# PL2303.net
KiCad netlist of a schematic drawn in Altium Designer
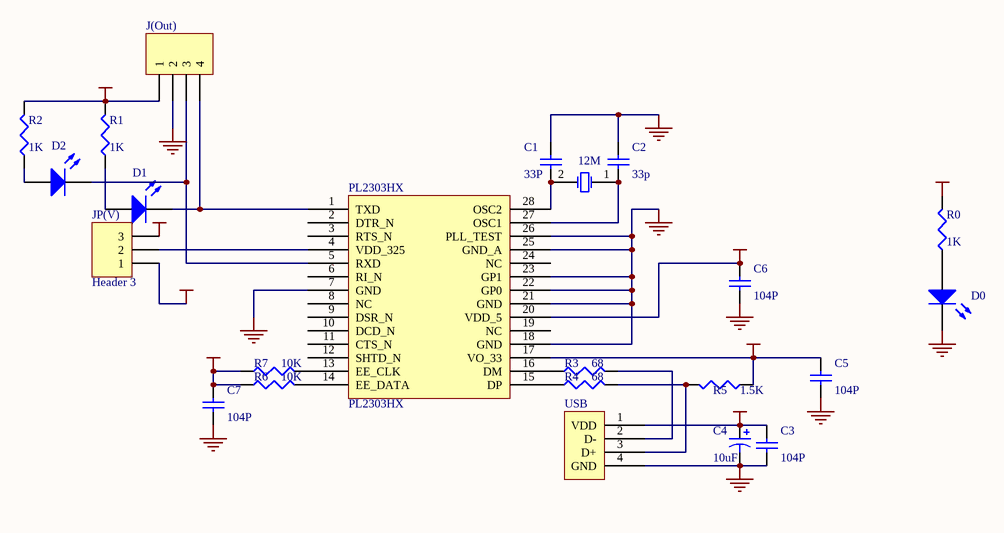
[diagram p0: PL2303.SchDoc]

(export (version "E")
  (design (tool "Eeschema 10.0.6"))
  (components
    (comp (ref "12M")
      (value "XTAL")
      (footprint "RAD-0.2")
      (description "Crystal Oscillator")
      (fields (field (name "PUBLISHER") "Altium Limited"))
      (libsource (lib "Miscellaneous Devices") (part "XTAL"))
    )
    (comp (ref "C1")
      (value "33P")
      (footprint "CR2012-0805")
      (description "Capacitor")
      (fields (field (name "Comment") "Cap") (field (name "PUBLISHER") "Altium Limited"))
      (libsource (lib "Miscellaneous Devices") (part "Cap"))
    )
    (comp (ref "C2")
      (value "33p")
      (footprint "CR2012-0805")
      (description "Capacitor")
      (fields (field (name "Comment") "Cap") (field (name "PUBLISHER") "Altium Limited"))
      (libsource (lib "Miscellaneous Devices") (part "Cap"))
    )
    (comp (ref "C3")
      (value "104P")
      (footprint "CR2012-0805")
      (description "Capacitor")
      (fields (field (name "Comment") "Cap") (field (name "PUBLISHER") "Altium Limited"))
      (libsource (lib "Miscellaneous Devices") (part "Cap"))
    )
    (comp (ref "C4")
      (value "10uF")
      (footprint "CR3225-1210")
      (description "Polarized Capacitor (Axial)")
      (fields (field (name "Comment") "Cap Pol2") (field (name "PUBLISHER") "Altium Limited"))
      (libsource (lib "Miscellaneous Devices") (part "Cap Pol2"))
    )
    (comp (ref "C5")
      (value "104P")
      (footprint "CR2012-0805")
      (description "Capacitor")
      (fields (field (name "Comment") "Cap") (field (name "PUBLISHER") "Altium Limited"))
      (libsource (lib "Miscellaneous Devices") (part "Cap"))
    )
    (comp (ref "C6")
      (value "104P")
      (footprint "CR2012-0805")
      (description "Capacitor")
      (fields (field (name "Comment") "Cap") (field (name "PUBLISHER") "Altium Limited"))
      (libsource (lib "Miscellaneous Devices") (part "Cap"))
    )
    (comp (ref "C7")
      (value "104P")
      (footprint "CR2012-0805")
      (description "Capacitor")
      (fields (field (name "Comment") "Cap") (field (name "PUBLISHER") "Altium Limited"))
      (libsource (lib "Miscellaneous Devices") (part "Cap"))
    )
    (comp (ref "D0")
      (value "LED2")
      (footprint "R2012-0805")
      (description "Typical RED, GREEN, YELLOW, AMBER GaAs LED")
      (fields (field (name "PUBLISHER") "Altium Limited"))
      (libsource (lib "Miscellaneous Devices") (part "LED2"))
    )
    (comp (ref "D1")
      (value "LED2")
      (footprint "R2012-0805")
      (description "Typical RED, GREEN, YELLOW, AMBER GaAs LED")
      (fields (field (name "PUBLISHER") "Altium Limited"))
      (libsource (lib "Miscellaneous Devices") (part "LED2"))
    )
    (comp (ref "D2")
      (value "LED2")
      (footprint "R2012-0805")
      (description "Typical RED, GREEN, YELLOW, AMBER GaAs LED")
      (fields (field (name "PUBLISHER") "Altium Limited"))
      (libsource (lib "Miscellaneous Devices") (part "LED2"))
    )
    (comp (ref "J(Out)")
      (value "Header 4")
      (footprint "HDR1X4")
      (description "Header, 4-Pin")
      (fields (field (name "PUBLISHER") "Altium Limited"))
      (libsource (lib "Miscellaneous Connectors") (part "Header 4"))
    )
    (comp (ref "JP(V)")
      (value "Header 3")
      (footprint "HDR1X3")
      (description "Header, 3-Pin")
      (fields (field (name "PUBLISHER") "Altium Limited"))
      (libsource (lib "Miscellaneous Connectors") (part "Header 3"))
    )
    (comp (ref "PL2303HX") (value "PL2303HX") (footprint "SSOP28") (libsource (lib "PL2303") (part "PL2303")))
    (comp (ref "R0")
      (value "1K")
      (footprint "R2012-0805")
      (description "Resistor")
      (fields (field (name "Comment") "Res3") (field (name "PUBLISHER") "Altium Limited"))
      (libsource (lib "Miscellaneous Devices") (part "Res3"))
    )
    (comp (ref "R1")
      (value "1K")
      (footprint "R2012-0805")
      (description "Resistor")
      (fields (field (name "Comment") "Res3") (field (name "PUBLISHER") "Altium Limited"))
      (libsource (lib "Miscellaneous Devices") (part "Res3"))
    )
    (comp (ref "R2")
      (value "1K")
      (footprint "R2012-0805")
      (description "Resistor")
      (fields (field (name "Comment") "Res3") (field (name "PUBLISHER") "Altium Limited"))
      (libsource (lib "Miscellaneous Devices") (part "Res3"))
    )
    (comp (ref "R3")
      (value "68")
      (footprint "CR2012-0805")
      (description "Resistor")
      (fields (field (name "Comment") "Res3") (field (name "PUBLISHER") "Altium Limited"))
      (libsource (lib "Miscellaneous Devices") (part "Res3"))
    )
    (comp (ref "R4")
      (value "68")
      (footprint "CR2012-0805")
      (description "Resistor")
      (fields (field (name "Comment") "Res3") (field (name "PUBLISHER") "Altium Limited"))
      (libsource (lib "Miscellaneous Devices") (part "Res3"))
    )
    (comp (ref "R5")
      (value "1.5K")
      (footprint "CR2012-0805")
      (description "Resistor")
      (fields (field (name "Comment") "Res3") (field (name "PUBLISHER") "Altium Limited"))
      (libsource (lib "Miscellaneous Devices") (part "Res3"))
    )
    (comp (ref "R6")
      (value "10K")
      (footprint "CR2012-0805")
      (description "Resistor")
      (fields (field (name "Comment") "Res3") (field (name "PUBLISHER") "Altium Limited"))
      (libsource (lib "Miscellaneous Devices") (part "Res3"))
    )
    (comp (ref "R7")
      (value "10K")
      (footprint "CR2012-0805")
      (description "Resistor")
      (fields (field (name "Comment") "Res3") (field (name "PUBLISHER") "Altium Limited"))
      (libsource (lib "Miscellaneous Devices") (part "Res3"))
    )
    (comp (ref "USB") (value "USB") (footprint "mini_USB") (libsource (lib "USB") (part "USB")))
  )
  (nets
    (net (code "1") (name "GND") (class "Default")
      (node (ref "C1") (pin "2") (pinfunction "2_2") (pintype "passive"))
      (node (ref "C2") (pin "2") (pinfunction "2_2") (pintype "passive"))
      (node (ref "C3") (pin "1") (pinfunction "1_1") (pintype "passive"))
      (node (ref "C4") (pin "2") (pinfunction "2_2") (pintype "passive"))
      (node (ref "C5") (pin "1") (pinfunction "1_1") (pintype "passive"))
      (node (ref "C6") (pin "1") (pinfunction "1_1") (pintype "passive"))
      (node (ref "C7") (pin "1") (pinfunction "1_1") (pintype "passive"))
      (node (ref "D0") (pin "2") (pinfunction "K_2") (pintype "passive"))
      (node (ref "J(Out)") (pin "2") (pinfunction "2_2") (pintype "passive"))
      (node (ref "PL2303HX") (pin "18") (pinfunction "GND_18") (pintype "passive"))
      (node (ref "PL2303HX") (pin "21") (pinfunction "GND_21") (pintype "passive"))
      (node (ref "PL2303HX") (pin "22") (pinfunction "GP0_22") (pintype "passive"))
      (node (ref "PL2303HX") (pin "23") (pinfunction "GP1_23") (pintype "passive"))
      (node (ref "PL2303HX") (pin "25") (pinfunction "GND_A_25") (pintype "passive"))
      (node (ref "PL2303HX") (pin "26") (pinfunction "PLL_TEST_26") (pintype "passive"))
      (node (ref "PL2303HX") (pin "7") (pinfunction "GND_7") (pintype "passive"))
      (node (ref "USB") (pin "4") (pinfunction "GND_4") (pintype "passive"))
    )
    (net (code "2") (name "Net-(12M-OSC1)") (class "Default")
      (node (ref "12M") (pin "1") (pinfunction "OSC1_1") (pintype "passive"))
      (node (ref "C2") (pin "1") (pinfunction "1_1") (pintype "passive"))
      (node (ref "PL2303HX") (pin "27") (pinfunction "OSC1_27") (pintype "passive"))
    )
    (net (code "3") (name "Net-(12M-OSC2)") (class "Default")
      (node (ref "12M") (pin "2") (pinfunction "OSC2_2") (pintype "passive"))
      (node (ref "C1") (pin "1") (pinfunction "1_1") (pintype "passive"))
      (node (ref "PL2303HX") (pin "28") (pinfunction "OSC2_28") (pintype "passive"))
    )
    (net (code "4") (name "Net-(D0-A)") (class "Default")
      (node (ref "D0") (pin "1") (pinfunction "A_1") (pintype "passive"))
      (node (ref "R0") (pin "1") (pinfunction "1_1") (pintype "passive"))
    )
    (net (code "5") (name "Net-(D1-A)") (class "Default")
      (node (ref "D1") (pin "1") (pinfunction "A_1") (pintype "passive"))
      (node (ref "R1") (pin "1") (pinfunction "1_1") (pintype "passive"))
    )
    (net (code "6") (name "Net-(D1-K)") (class "Default")
      (node (ref "D1") (pin "2") (pinfunction "K_2") (pintype "passive"))
      (node (ref "J(Out)") (pin "4") (pinfunction "4_4") (pintype "passive"))
      (node (ref "PL2303HX") (pin "1") (pinfunction "TXD_1") (pintype "passive"))
    )
    (net (code "7") (name "Net-(D2-A)") (class "Default")
      (node (ref "D2") (pin "1") (pinfunction "A_1") (pintype "passive"))
      (node (ref "R2") (pin "1") (pinfunction "1_1") (pintype "passive"))
    )
    (net (code "8") (name "Net-(D2-K)") (class "Default")
      (node (ref "D2") (pin "2") (pinfunction "K_2") (pintype "passive"))
      (node (ref "J(Out)") (pin "3") (pinfunction "3_3") (pintype "passive"))
      (node (ref "PL2303HX") (pin "5") (pinfunction "RXD_5") (pintype "passive"))
    )
    (net (code "9") (name "Net-(PL2303HX-DM)") (class "Default")
      (node (ref "PL2303HX") (pin "16") (pinfunction "DM_16") (pintype "passive"))
      (node (ref "R3") (pin "1") (pinfunction "1_1") (pintype "passive"))
    )
    (net (code "10") (name "Net-(PL2303HX-DP)") (class "Default")
      (node (ref "PL2303HX") (pin "15") (pinfunction "DP_15") (pintype "passive"))
      (node (ref "R4") (pin "1") (pinfunction "1_1") (pintype "passive"))
    )
    (net (code "11") (name "Net-(PL2303HX-EE_CLK)") (class "Default")
      (node (ref "PL2303HX") (pin "13") (pinfunction "EE_CLK_13") (pintype "passive"))
      (node (ref "R7") (pin "2") (pinfunction "2_2") (pintype "passive"))
    )
    (net (code "12") (name "Net-(PL2303HX-EE_DATA)") (class "Default")
      (node (ref "PL2303HX") (pin "14") (pinfunction "EE_DATA_14") (pintype "passive"))
      (node (ref "R6") (pin "2") (pinfunction "2_2") (pintype "passive"))
    )
    (net (code "13") (name "Net-(PL2303HX-VDD_325)") (class "Default")
      (node (ref "JP(V)") (pin "2") (pinfunction "2_2") (pintype "passive"))
      (node (ref "PL2303HX") (pin "4") (pinfunction "VDD_325_4") (pintype "passive"))
    )
    (net (code "14") (name "Net-(USB-D+)") (class "Default")
      (node (ref "R4") (pin "2") (pinfunction "2_2") (pintype "passive"))
      (node (ref "R5") (pin "2") (pinfunction "2_2") (pintype "passive"))
      (node (ref "USB") (pin "3") (pinfunction "D+_3") (pintype "passive"))
    )
    (net (code "15") (name "Net-(USB-D-)") (class "Default")
      (node (ref "R3") (pin "2") (pinfunction "2_2") (pintype "passive"))
      (node (ref "USB") (pin "2") (pinfunction "D-_2") (pintype "passive"))
    )
    (net (code "16") (name "VDD") (class "Default")
      (node (ref "C3") (pin "2") (pinfunction "2_2") (pintype "passive"))
      (node (ref "C4") (pin "1") (pinfunction "1_1") (pintype "passive"))
      (node (ref "C6") (pin "2") (pinfunction "2_2") (pintype "passive"))
      (node (ref "C7") (pin "2") (pinfunction "2_2") (pintype "passive"))
      (node (ref "J(Out)") (pin "1") (pinfunction "1_1") (pintype "passive"))
      (node (ref "JP(V)") (pin "3") (pinfunction "3_3") (pintype "passive"))
      (node (ref "PL2303HX") (pin "20") (pinfunction "VDD_5_20") (pintype "passive"))
      (node (ref "R0") (pin "2") (pinfunction "2_2") (pintype "passive"))
      (node (ref "R1") (pin "2") (pinfunction "2_2") (pintype "passive"))
      (node (ref "R2") (pin "2") (pinfunction "2_2") (pintype "passive"))
      (node (ref "R6") (pin "1") (pinfunction "1_1") (pintype "passive"))
      (node (ref "R7") (pin "1") (pinfunction "1_1") (pintype "passive"))
      (node (ref "USB") (pin "1") (pinfunction "VDD_1") (pintype "passive"))
    )
    (net (code "17") (name "VDD3.3") (class "Default")
      (node (ref "C5") (pin "2") (pinfunction "2_2") (pintype "passive"))
      (node (ref "JP(V)") (pin "1") (pinfunction "1_1") (pintype "passive"))
      (node (ref "PL2303HX") (pin "17") (pinfunction "VO_33_17") (pintype "passive"))
      (node (ref "R5") (pin "1") (pinfunction "1_1") (pintype "passive"))
    )
    (net (code "18") (name "unconnected-(PL2303HX-CTS_N-Pad11)") (class "Default")
      (node (ref "PL2303HX") (pin "11") (pinfunction "CTS_N_11") (pintype "passive"))
    )
    (net (code "19") (name "unconnected-(PL2303HX-DCD_N-Pad10)") (class "Default")
      (node (ref "PL2303HX") (pin "10") (pinfunction "DCD_N_10") (pintype "passive"))
    )
    (net (code "20") (name "unconnected-(PL2303HX-DSR_N-Pad9)") (class "Default")
      (node (ref "PL2303HX") (pin "9") (pinfunction "DSR_N_9") (pintype "passive"))
    )
    (net (code "21") (name "unconnected-(PL2303HX-DTR_N-Pad2)") (class "Default")
      (node (ref "PL2303HX") (pin "2") (pinfunction "DTR_N_2") (pintype "passive"))
    )
    (net (code "22") (name "unconnected-(PL2303HX-NC-Pad8)") (class "Default")
      (node (ref "PL2303HX") (pin "8") (pinfunction "NC_8") (pintype "passive"))
    )
    (net (code "23") (name "unconnected-(PL2303HX-NC-Pad19)") (class "Default")
      (node (ref "PL2303HX") (pin "19") (pinfunction "NC_19") (pintype "passive"))
    )
    (net (code "24") (name "unconnected-(PL2303HX-NC-Pad24)") (class "Default")
      (node (ref "PL2303HX") (pin "24") (pinfunction "NC_24") (pintype "passive"))
    )
    (net (code "25") (name "unconnected-(PL2303HX-RI_N-Pad6)") (class "Default")
      (node (ref "PL2303HX") (pin "6") (pinfunction "RI_N_6") (pintype "passive"))
    )
    (net (code "26") (name "unconnected-(PL2303HX-RTS_N-Pad3)") (class "Default")
      (node (ref "PL2303HX") (pin "3") (pinfunction "RTS_N_3") (pintype "passive"))
    )
    (net (code "27") (name "unconnected-(PL2303HX-SHTD_N-Pad12)") (class "Default")
      (node (ref "PL2303HX") (pin "12") (pinfunction "SHTD_N_12") (pintype "passive"))
    )
  )
)
